# Line_sensors_-_6.net
KiCad netlist of a schematic drawn in EAGLE
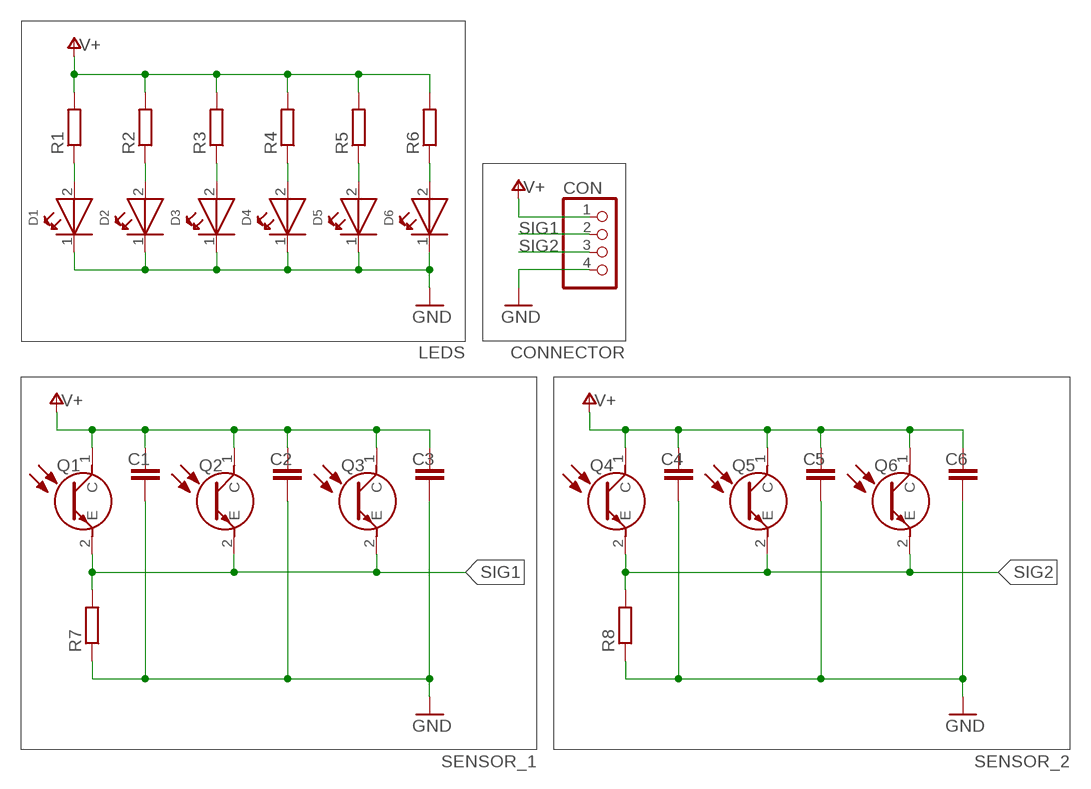
[diagram p0: schematic, sheet 1]

(export (version "E")
  (design (tool "Eeschema 10.0.6"))
  (components
    (comp (ref "C1")
      (value "C-EUC0805")
      (footprint "eagle-import:C0805")
      (libsource (lib "eagle-import") (part "C-EUC0805"))
    )
    (comp (ref "C2")
      (value "C-EUC0805")
      (footprint "eagle-import:C0805")
      (libsource (lib "eagle-import") (part "C-EUC0805"))
    )
    (comp (ref "C3")
      (value "C-EUC0805")
      (footprint "eagle-import:C0805")
      (libsource (lib "eagle-import") (part "C-EUC0805"))
    )
    (comp (ref "C4")
      (value "C-EUC0805")
      (footprint "eagle-import:C0805")
      (libsource (lib "eagle-import") (part "C-EUC0805"))
    )
    (comp (ref "C5")
      (value "C-EUC0805")
      (footprint "eagle-import:C0805")
      (libsource (lib "eagle-import") (part "C-EUC0805"))
    )
    (comp (ref "C6")
      (value "C-EUC0805")
      (footprint "eagle-import:C0805")
      (libsource (lib "eagle-import") (part "C-EUC0805"))
    )
    (comp (ref "CON")
      (value "PINHD-1X4")
      (footprint "eagle-import:1X04")
      (libsource (lib "eagle-import") (part "PINHD-1X4"))
    )
    (comp (ref "D1")
      (value "WL-SMTW-150141AS73100-A")
      (footprint "eagle-import:3528-2PIN")
      (fields
        (field (name "MANUFACTURER") "Würth Elektronik eiSos GmbH")
        (field (name "CREATED-BY") "Christin Otto")
      )
      (libsource (lib "eagle-import") (part "WL-SMTW-150141AS73100-A"))
    )
    (comp (ref "D2")
      (value "WL-SMTW-150141AS73100-A")
      (footprint "eagle-import:3528-2PIN")
      (fields
        (field (name "MANUFACTURER") "Würth Elektronik eiSos GmbH")
        (field (name "CREATED-BY") "Christin Otto")
      )
      (libsource (lib "eagle-import") (part "WL-SMTW-150141AS73100-A"))
    )
    (comp (ref "D3")
      (value "WL-SMTW-150141AS73100-A")
      (footprint "eagle-import:3528-2PIN")
      (fields
        (field (name "MANUFACTURER") "Würth Elektronik eiSos GmbH")
        (field (name "CREATED-BY") "Christin Otto")
      )
      (libsource (lib "eagle-import") (part "WL-SMTW-150141AS73100-A"))
    )
    (comp (ref "D4")
      (value "WL-SMTW-150141AS73100-A")
      (footprint "eagle-import:3528-2PIN")
      (fields
        (field (name "MANUFACTURER") "Würth Elektronik eiSos GmbH")
        (field (name "CREATED-BY") "Christin Otto")
      )
      (libsource (lib "eagle-import") (part "WL-SMTW-150141AS73100-A"))
    )
    (comp (ref "D5")
      (value "WL-SMTW-150141AS73100-A")
      (footprint "eagle-import:3528-2PIN")
      (fields
        (field (name "MANUFACTURER") "Würth Elektronik eiSos GmbH")
        (field (name "CREATED-BY") "Christin Otto")
      )
      (libsource (lib "eagle-import") (part "WL-SMTW-150141AS73100-A"))
    )
    (comp (ref "D6")
      (value "WL-SMTW-150141AS73100-A")
      (footprint "eagle-import:3528-2PIN")
      (fields
        (field (name "MANUFACTURER") "Würth Elektronik eiSos GmbH")
        (field (name "CREATED-BY") "Christin Otto")
      )
      (libsource (lib "eagle-import") (part "WL-SMTW-150141AS73100-A"))
    )
    (comp (ref "Q1")
      (value "VEMT2520X01")
      (footprint "eagle-import:VEMT2520X01")
      (fields
        (field (name "MOUSER_PART_NUMBER") "782-VEMT2520X01")
        (field (name "RS_PART_NUMBER") "7689417P")
      )
      (libsource (lib "eagle-import") (part "VEMT2520X01"))
    )
    (comp (ref "Q2")
      (value "VEMT2520X01")
      (footprint "eagle-import:VEMT2520X01")
      (fields
        (field (name "MOUSER_PART_NUMBER") "782-VEMT2520X01")
        (field (name "RS_PART_NUMBER") "7689417P")
      )
      (libsource (lib "eagle-import") (part "VEMT2520X01"))
    )
    (comp (ref "Q3")
      (value "VEMT2520X01")
      (footprint "eagle-import:VEMT2520X01")
      (fields
        (field (name "MOUSER_PART_NUMBER") "782-VEMT2520X01")
        (field (name "RS_PART_NUMBER") "7689417P")
      )
      (libsource (lib "eagle-import") (part "VEMT2520X01"))
    )
    (comp (ref "Q4")
      (value "VEMT2520X01")
      (footprint "eagle-import:VEMT2520X01")
      (fields
        (field (name "MOUSER_PART_NUMBER") "782-VEMT2520X01")
        (field (name "RS_PART_NUMBER") "7689417P")
      )
      (libsource (lib "eagle-import") (part "VEMT2520X01"))
    )
    (comp (ref "Q5")
      (value "VEMT2520X01")
      (footprint "eagle-import:VEMT2520X01")
      (fields
        (field (name "MOUSER_PART_NUMBER") "782-VEMT2520X01")
        (field (name "RS_PART_NUMBER") "7689417P")
      )
      (libsource (lib "eagle-import") (part "VEMT2520X01"))
    )
    (comp (ref "Q6")
      (value "VEMT2520X01")
      (footprint "eagle-import:VEMT2520X01")
      (fields
        (field (name "MOUSER_PART_NUMBER") "782-VEMT2520X01")
        (field (name "RS_PART_NUMBER") "7689417P")
      )
      (libsource (lib "eagle-import") (part "VEMT2520X01"))
    )
    (comp (ref "R1")
      (value "R-EU_R0805")
      (footprint "eagle-import:R0805")
      (libsource (lib "eagle-import") (part "R-EU_R0805"))
    )
    (comp (ref "R2")
      (value "R-EU_R0805")
      (footprint "eagle-import:R0805")
      (libsource (lib "eagle-import") (part "R-EU_R0805"))
    )
    (comp (ref "R3")
      (value "R-EU_R0805")
      (footprint "eagle-import:R0805")
      (libsource (lib "eagle-import") (part "R-EU_R0805"))
    )
    (comp (ref "R4")
      (value "R-EU_R0805")
      (footprint "eagle-import:R0805")
      (libsource (lib "eagle-import") (part "R-EU_R0805"))
    )
    (comp (ref "R5")
      (value "R-EU_R0805")
      (footprint "eagle-import:R0805")
      (libsource (lib "eagle-import") (part "R-EU_R0805"))
    )
    (comp (ref "R6")
      (value "R-EU_R0805")
      (footprint "eagle-import:R0805")
      (libsource (lib "eagle-import") (part "R-EU_R0805"))
    )
    (comp (ref "R7")
      (value "R-EU_R0805")
      (footprint "eagle-import:R0805")
      (libsource (lib "eagle-import") (part "R-EU_R0805"))
    )
    (comp (ref "R8")
      (value "R-EU_R0805")
      (footprint "eagle-import:R0805")
      (libsource (lib "eagle-import") (part "R-EU_R0805"))
    )
  )
  (nets
    (net (code "1") (name "GND") (class "Default")
      (node (ref "C1") (pin "2") (pinfunction "2_2") (pintype "passive"))
      (node (ref "C2") (pin "2") (pinfunction "2_2") (pintype "passive"))
      (node (ref "C3") (pin "2") (pinfunction "2_2") (pintype "passive"))
      (node (ref "C4") (pin "2") (pinfunction "2_2") (pintype "passive"))
      (node (ref "C5") (pin "2") (pinfunction "2_2") (pintype "passive"))
      (node (ref "C6") (pin "2") (pinfunction "2_2") (pintype "passive"))
      (node (ref "CON") (pin "4") (pinfunction "4_4") (pintype "passive"))
      (node (ref "D1") (pin "1") (pinfunction "K_1") (pintype "bidirectional"))
      (node (ref "D2") (pin "1") (pinfunction "K_1") (pintype "bidirectional"))
      (node (ref "D3") (pin "1") (pinfunction "K_1") (pintype "bidirectional"))
      (node (ref "D4") (pin "1") (pinfunction "K_1") (pintype "bidirectional"))
      (node (ref "D5") (pin "1") (pinfunction "K_1") (pintype "bidirectional"))
      (node (ref "D6") (pin "1") (pinfunction "K_1") (pintype "bidirectional"))
      (node (ref "R7") (pin "1") (pinfunction "1_1") (pintype "passive"))
      (node (ref "R8") (pin "1") (pinfunction "1_1") (pintype "passive"))
    )
    (net (code "2") (name "Net-(D1-A)") (class "Default")
      (node (ref "D1") (pin "2") (pinfunction "A_2") (pintype "bidirectional"))
      (node (ref "R1") (pin "1") (pinfunction "1_1") (pintype "passive"))
    )
    (net (code "3") (name "Net-(D2-A)") (class "Default")
      (node (ref "D2") (pin "2") (pinfunction "A_2") (pintype "bidirectional"))
      (node (ref "R2") (pin "1") (pinfunction "1_1") (pintype "passive"))
    )
    (net (code "4") (name "Net-(D3-A)") (class "Default")
      (node (ref "D3") (pin "2") (pinfunction "A_2") (pintype "bidirectional"))
      (node (ref "R3") (pin "1") (pinfunction "1_1") (pintype "passive"))
    )
    (net (code "5") (name "Net-(D4-A)") (class "Default")
      (node (ref "D4") (pin "2") (pinfunction "A_2") (pintype "bidirectional"))
      (node (ref "R4") (pin "1") (pinfunction "1_1") (pintype "passive"))
    )
    (net (code "6") (name "Net-(D5-A)") (class "Default")
      (node (ref "D5") (pin "2") (pinfunction "A_2") (pintype "bidirectional"))
      (node (ref "R5") (pin "1") (pinfunction "1_1") (pintype "passive"))
    )
    (net (code "7") (name "Net-(D6-A)") (class "Default")
      (node (ref "D6") (pin "2") (pinfunction "A_2") (pintype "bidirectional"))
      (node (ref "R6") (pin "1") (pinfunction "1_1") (pintype "passive"))
    )
    (net (code "8") (name "SIG1") (class "Default")
      (node (ref "CON") (pin "2") (pinfunction "2_2") (pintype "passive"))
      (node (ref "Q1") (pin "2") (pinfunction "E_2") (pintype "bidirectional"))
      (node (ref "Q2") (pin "2") (pinfunction "E_2") (pintype "bidirectional"))
      (node (ref "Q3") (pin "2") (pinfunction "E_2") (pintype "bidirectional"))
      (node (ref "R7") (pin "2") (pinfunction "2_2") (pintype "passive"))
    )
    (net (code "9") (name "SIG2") (class "Default")
      (node (ref "CON") (pin "3") (pinfunction "3_3") (pintype "passive"))
      (node (ref "Q4") (pin "2") (pinfunction "E_2") (pintype "bidirectional"))
      (node (ref "Q5") (pin "2") (pinfunction "E_2") (pintype "bidirectional"))
      (node (ref "Q6") (pin "2") (pinfunction "E_2") (pintype "bidirectional"))
      (node (ref "R8") (pin "2") (pinfunction "2_2") (pintype "passive"))
    )
    (net (code "10") (name "V+") (class "Default")
      (node (ref "C1") (pin "1") (pinfunction "1_1") (pintype "passive"))
      (node (ref "C2") (pin "1") (pinfunction "1_1") (pintype "passive"))
      (node (ref "C3") (pin "1") (pinfunction "1_1") (pintype "passive"))
      (node (ref "C4") (pin "1") (pinfunction "1_1") (pintype "passive"))
      (node (ref "C5") (pin "1") (pinfunction "1_1") (pintype "passive"))
      (node (ref "C6") (pin "1") (pinfunction "1_1") (pintype "passive"))
      (node (ref "CON") (pin "1") (pinfunction "1_1") (pintype "passive"))
      (node (ref "Q1") (pin "1") (pinfunction "C_1") (pintype "bidirectional"))
      (node (ref "Q2") (pin "1") (pinfunction "C_1") (pintype "bidirectional"))
      (node (ref "Q3") (pin "1") (pinfunction "C_1") (pintype "bidirectional"))
      (node (ref "Q4") (pin "1") (pinfunction "C_1") (pintype "bidirectional"))
      (node (ref "Q5") (pin "1") (pinfunction "C_1") (pintype "bidirectional"))
      (node (ref "Q6") (pin "1") (pinfunction "C_1") (pintype "bidirectional"))
      (node (ref "R1") (pin "2") (pinfunction "2_2") (pintype "passive"))
      (node (ref "R2") (pin "2") (pinfunction "2_2") (pintype "passive"))
      (node (ref "R3") (pin "2") (pinfunction "2_2") (pintype "passive"))
      (node (ref "R4") (pin "2") (pinfunction "2_2") (pintype "passive"))
      (node (ref "R5") (pin "2") (pinfunction "2_2") (pintype "passive"))
      (node (ref "R6") (pin "2") (pinfunction "2_2") (pintype "passive"))
    )
  )
)
